# Snap4_audio.net
KiCad netlist of a schematic drawn in Altium Designer
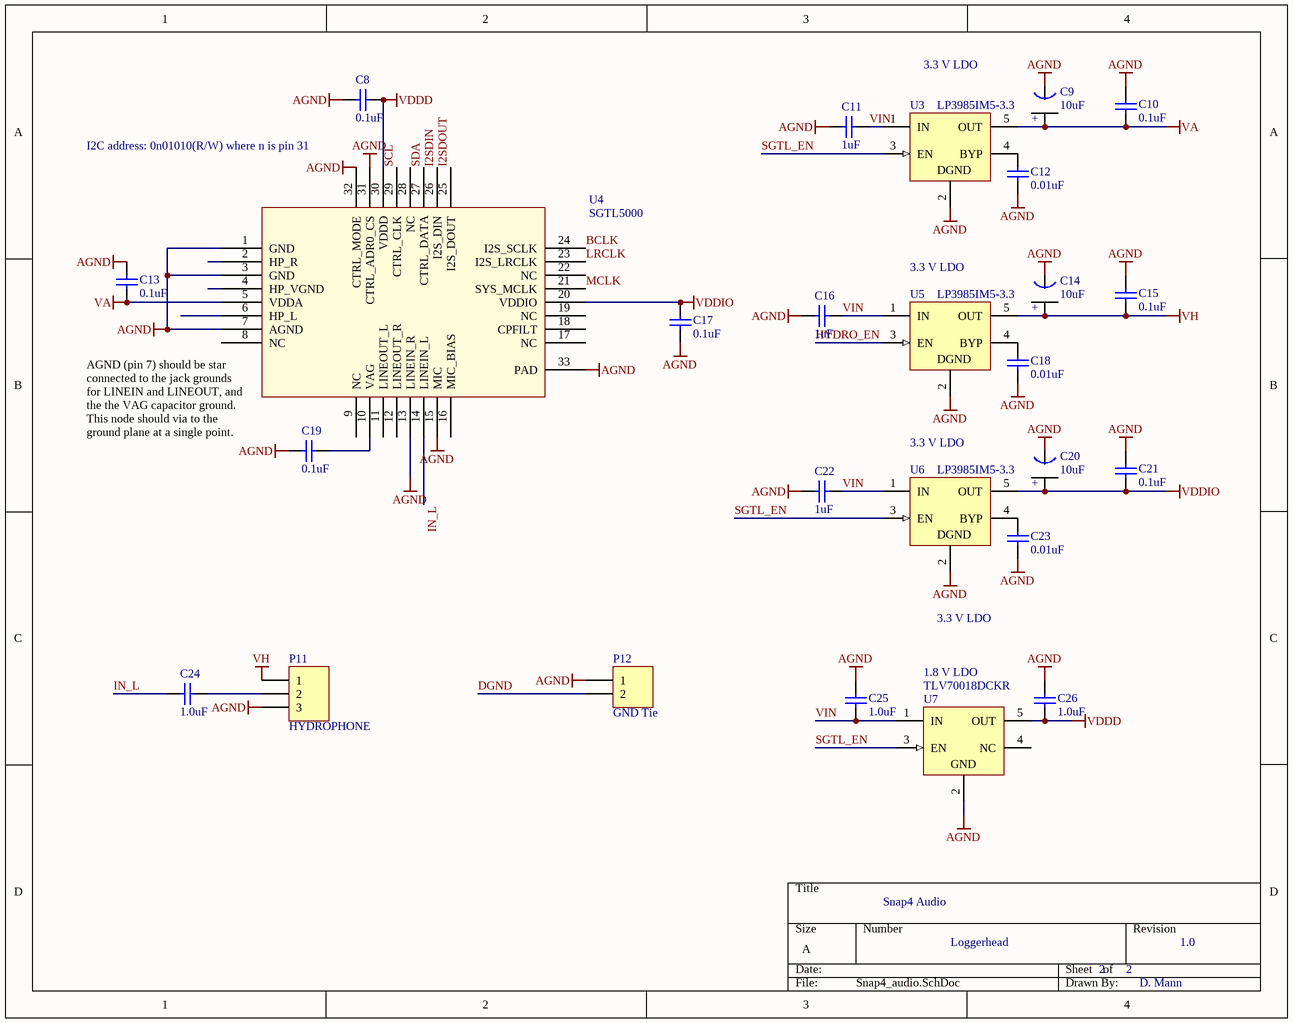
[diagram p0: Snap4_audio.SchDoc]

(export (version "E")
  (design (tool "Eeschema 10.0.6"))
  (components
    (comp (ref "C8")
      (value "0.1uF")
      (footprint "0402")
      (description "Ceramic Chip Capacitor - Standard")
      (fields (field (name "PUBLISHER") "Altium Limited"))
      (libsource (lib "KEMET Chip Capacitor") (part "C0402"))
    )
    (comp (ref "C9") (value "10uF") (footprint "Tant0805") (libsource (lib "Loggerhead") (part "Tant0805")))
    (comp (ref "C10")
      (value "0.1uF")
      (footprint "0402")
      (description "Ceramic Chip Capacitor - Standard")
      (fields (field (name "PUBLISHER") "Altium Limited"))
      (libsource (lib "KEMET Chip Capacitor") (part "C0402"))
    )
    (comp (ref "C11")
      (value "1uF")
      (footprint "0402")
      (description "Ceramic Chip Capacitor - Standard")
      (fields (field (name "PUBLISHER") "Altium Limited"))
      (libsource (lib "KEMET Chip Capacitor") (part "C0402"))
    )
    (comp (ref "C12")
      (value "0.01uF")
      (footprint "0402")
      (description "Ceramic Chip Capacitor - Standard")
      (fields (field (name "PUBLISHER") "Altium Limited"))
      (libsource (lib "KEMET Chip Capacitor") (part "C0402"))
    )
    (comp (ref "C13")
      (value "0.1uF")
      (footprint "0402")
      (description "Ceramic Chip Capacitor - Standard")
      (fields (field (name "PUBLISHER") "Altium Limited"))
      (libsource (lib "KEMET Chip Capacitor") (part "C0402"))
    )
    (comp (ref "C14") (value "10uF") (footprint "Tant0805") (libsource (lib "Loggerhead") (part "Tant0805")))
    (comp (ref "C15")
      (value "0.1uF")
      (footprint "0402")
      (description "Ceramic Chip Capacitor - Standard")
      (fields (field (name "PUBLISHER") "Altium Limited"))
      (libsource (lib "KEMET Chip Capacitor") (part "C0402"))
    )
    (comp (ref "C16")
      (value "1uF")
      (footprint "0402")
      (description "Ceramic Chip Capacitor - Standard")
      (fields (field (name "PUBLISHER") "Altium Limited"))
      (libsource (lib "KEMET Chip Capacitor") (part "C0402"))
    )
    (comp (ref "C17")
      (value "0.1uF")
      (footprint "0402")
      (description "Ceramic Chip Capacitor - Standard")
      (fields (field (name "PUBLISHER") "Altium Limited"))
      (libsource (lib "KEMET Chip Capacitor") (part "C0402"))
    )
    (comp (ref "C18")
      (value "0.01uF")
      (footprint "0402")
      (description "Ceramic Chip Capacitor - Standard")
      (fields (field (name "PUBLISHER") "Altium Limited"))
      (libsource (lib "KEMET Chip Capacitor") (part "C0402"))
    )
    (comp (ref "C19")
      (value "0.1uF")
      (footprint "0402")
      (description "Ceramic Chip Capacitor - Standard")
      (fields (field (name "PUBLISHER") "Altium Limited"))
      (libsource (lib "KEMET Chip Capacitor") (part "C0402"))
    )
    (comp (ref "C20") (value "10uF") (footprint "Tant0805") (libsource (lib "Loggerhead") (part "Tant0805")))
    (comp (ref "C21")
      (value "0.1uF")
      (footprint "0402")
      (description "Ceramic Chip Capacitor - Standard")
      (fields (field (name "PUBLISHER") "Altium Limited"))
      (libsource (lib "KEMET Chip Capacitor") (part "C0402"))
    )
    (comp (ref "C22")
      (value "1uF")
      (footprint "0402")
      (description "Ceramic Chip Capacitor - Standard")
      (fields (field (name "PUBLISHER") "Altium Limited"))
      (libsource (lib "KEMET Chip Capacitor") (part "C0402"))
    )
    (comp (ref "C23")
      (value "0.01uF")
      (footprint "0402")
      (description "Ceramic Chip Capacitor - Standard")
      (fields (field (name "PUBLISHER") "Altium Limited"))
      (libsource (lib "KEMET Chip Capacitor") (part "C0402"))
    )
    (comp (ref "C24")
      (value "1.0uF")
      (footprint "0402")
      (description "Ceramic Chip Capacitor - Standard")
      (fields (field (name "PUBLISHER") "Altium Limited"))
      (libsource (lib "KEMET Chip Capacitor") (part "C0402"))
    )
    (comp (ref "C25")
      (value "1.0uF")
      (footprint "0402")
      (description "Ceramic Chip Capacitor - Standard")
      (fields (field (name "PUBLISHER") "Altium Limited"))
      (libsource (lib "KEMET Chip Capacitor") (part "C0402"))
    )
    (comp (ref "C26")
      (value "1.0uF")
      (footprint "0402")
      (description "Ceramic Chip Capacitor - Standard")
      (fields (field (name "PUBLISHER") "Altium Limited"))
      (libsource (lib "KEMET Chip Capacitor") (part "C0402"))
    )
    (comp (ref "P11")
      (value "HYDROPHONE")
      (footprint "HDR1X3")
      (description "Header, 3-Pin")
      (fields (field (name "PUBLISHER") "Altium Limited"))
      (libsource (lib "Miscellaneous Connectors") (part "Header 3"))
    )
    (comp (ref "P12")
      (value "GND Tie")
      (footprint "HDR1X2")
      (description "Header, 2-Pin")
      (fields (field (name "PUBLISHER") "Altium Limited"))
      (libsource (lib "Miscellaneous Connectors") (part "Header 2"))
    )
    (comp (ref "U3")
      (value "LP3985IM5-3.3")
      (footprint "MF05A_N")
      (description "Micropower, 150mA Low-Noise Ultra Low-Dropout CMOS Voltage Regulator")
      (fields
        (field (name "MANUFACTURER") "National Semiconductor")
        (field (name "DIGIKEYPARTNUMBER") "LP3985IM5-3.3CT-ND")
        (field (name "PUBLISHER") "Altium Limited")
      )
      (libsource (lib "NSC LDO") (part "LP3985IM5-3.3"))
    )
    (comp (ref "U4") (value "SGTL5000") (footprint "QFN32") (libsource (lib "Loggerhead") (part "SGTL5000")))
    (comp (ref "U5")
      (value "LP3985IM5-3.3")
      (footprint "MF05A_N")
      (description "Micropower, 150mA Low-Noise Ultra Low-Dropout CMOS Voltage Regulator")
      (fields
        (field (name "MANUFACTURER") "National Semiconductor")
        (field (name "DIGIKEYPARTNUMBER") "LP3985IM5-3.3CT-ND")
        (field (name "PUBLISHER") "Altium Limited")
      )
      (libsource (lib "NSC LDO") (part "LP3985IM5-3.3"))
    )
    (comp (ref "U6")
      (value "LP3985IM5-3.3")
      (footprint "MF05A_N")
      (description "Micropower, 150mA Low-Noise Ultra Low-Dropout CMOS Voltage Regulator")
      (fields
        (field (name "MANUFACTURER") "National Semiconductor")
        (field (name "DIGIKEYPARTNUMBER") "LP3985IM5-3.3CT-ND")
        (field (name "PUBLISHER") "Altium Limited")
      )
      (libsource (lib "NSC LDO") (part "LP3985IM5-3.3"))
    )
    (comp (ref "U7")
      (value "TLV70018DCKR")
      (footprint "TI-DCK5_V")
      (fields (field (name "MANUFACTURER") "Texas Instruments"))
      (libsource (lib "TI Power Management Linear Regulator Single Channel LDO (0-350mA)") (part "TLV70018DCKR"))
    )
  )
  (nets
    (net (code "1") (name "/BCLK") (class "Default")
      (node (ref "U4") (pin "24") (pinfunction "I2S_SCLK_24") (pintype "passive"))
    )
    (net (code "2") (name "/DGND") (class "Default")
      (node (ref "P12") (pin "2") (pinfunction "2_2") (pintype "passive"))
    )
    (net (code "3") (name "/HYDRO_EN") (class "Default")
      (node (ref "U5") (pin "3") (pinfunction "EN_3") (pintype "input"))
    )
    (net (code "4") (name "/I2SDIN") (class "Default")
      (node (ref "U4") (pin "26") (pinfunction "I2S_DIN_26") (pintype "passive"))
    )
    (net (code "5") (name "/I2SDOUT") (class "Default")
      (node (ref "U4") (pin "25") (pinfunction "I2S_DOUT_25") (pintype "passive"))
    )
    (net (code "6") (name "/IN_L") (class "Default")
      (node (ref "C24") (pin "2") (pinfunction "2_2") (pintype "passive"))
      (node (ref "U4") (pin "14") (pinfunction "LINEIN_L_14") (pintype "passive"))
    )
    (net (code "7") (name "/LRCLK") (class "Default")
      (node (ref "U4") (pin "23") (pinfunction "I2S_LRCLK_23") (pintype "passive"))
    )
    (net (code "8") (name "/MCLK") (class "Default")
      (node (ref "U4") (pin "21") (pinfunction "SYS_MCLK_21") (pintype "passive"))
    )
    (net (code "9") (name "/SCL") (class "Default")
      (node (ref "U4") (pin "29") (pinfunction "CTRL_CLK_29") (pintype "passive"))
    )
    (net (code "10") (name "/SDA") (class "Default")
      (node (ref "U4") (pin "27") (pinfunction "CTRL_DATA_27") (pintype "passive"))
    )
    (net (code "11") (name "/SGTL_EN") (class "Default")
      (node (ref "U3") (pin "3") (pinfunction "EN_3") (pintype "input"))
      (node (ref "U6") (pin "3") (pinfunction "EN_3") (pintype "input"))
      (node (ref "U7") (pin "3") (pinfunction "EN_3") (pintype "input"))
    )
    (net (code "12") (name "/VIN") (class "Default")
      (node (ref "C11") (pin "1") (pinfunction "1_1") (pintype "passive"))
      (node (ref "C16") (pin "1") (pinfunction "1_1") (pintype "passive"))
      (node (ref "C22") (pin "1") (pinfunction "1_1") (pintype "passive"))
      (node (ref "C25") (pin "1") (pinfunction "1_1") (pintype "passive"))
      (node (ref "U3") (pin "1") (pinfunction "IN_1") (pintype "power_in"))
      (node (ref "U5") (pin "1") (pinfunction "IN_1") (pintype "power_in"))
      (node (ref "U6") (pin "1") (pinfunction "IN_1") (pintype "power_in"))
      (node (ref "U7") (pin "1") (pinfunction "IN_1") (pintype "power_in"))
    )
    (net (code "13") (name "AGND") (class "Default")
      (node (ref "C10") (pin "2") (pinfunction "2_2") (pintype "passive"))
      (node (ref "C11") (pin "2") (pinfunction "2_2") (pintype "passive"))
      (node (ref "C12") (pin "2") (pinfunction "2_2") (pintype "passive"))
      (node (ref "C13") (pin "2") (pinfunction "2_2") (pintype "passive"))
      (node (ref "C14") (pin "1") (pinfunction "GND_1") (pintype "passive"))
      (node (ref "C15") (pin "2") (pinfunction "2_2") (pintype "passive"))
      (node (ref "C16") (pin "2") (pinfunction "2_2") (pintype "passive"))
      (node (ref "C17") (pin "2") (pinfunction "2_2") (pintype "passive"))
      (node (ref "C18") (pin "2") (pinfunction "2_2") (pintype "passive"))
      (node (ref "C19") (pin "2") (pinfunction "2_2") (pintype "passive"))
      (node (ref "C20") (pin "1") (pinfunction "GND_1") (pintype "passive"))
      (node (ref "C21") (pin "2") (pinfunction "2_2") (pintype "passive"))
      (node (ref "C22") (pin "2") (pinfunction "2_2") (pintype "passive"))
      (node (ref "C23") (pin "2") (pinfunction "2_2") (pintype "passive"))
      (node (ref "C25") (pin "2") (pinfunction "2_2") (pintype "passive"))
      (node (ref "C26") (pin "2") (pinfunction "2_2") (pintype "passive"))
      (node (ref "C8") (pin "2") (pinfunction "2_2") (pintype "passive"))
      (node (ref "C9") (pin "1") (pinfunction "GND_1") (pintype "passive"))
      (node (ref "P11") (pin "3") (pinfunction "3_3") (pintype "passive"))
      (node (ref "P12") (pin "1") (pinfunction "1_1") (pintype "passive"))
      (node (ref "U3") (pin "2") (pinfunction "GND_2") (pintype "power_in"))
      (node (ref "U4") (pin "1") (pinfunction "GND_1") (pintype "passive"))
      (node (ref "U4") (pin "13") (pinfunction "LINEIN_R_13") (pintype "passive"))
      (node (ref "U4") (pin "15") (pinfunction "MIC_15") (pintype "passive"))
      (node (ref "U4") (pin "3") (pinfunction "GND_3") (pintype "passive"))
      (node (ref "U4") (pin "31") (pinfunction "CTRL_ADR0_CS_31") (pintype "passive"))
      (node (ref "U4") (pin "32") (pinfunction "CTRL_MODE_32") (pintype "passive"))
      (node (ref "U4") (pin "33") (pinfunction "PAD_33") (pintype "passive"))
      (node (ref "U4") (pin "7") (pinfunction "AGND_7") (pintype "passive"))
      (node (ref "U5") (pin "2") (pinfunction "GND_2") (pintype "power_in"))
      (node (ref "U6") (pin "2") (pinfunction "GND_2") (pintype "power_in"))
      (node (ref "U7") (pin "2") (pinfunction "GND_2") (pintype "power_in"))
    )
    (net (code "14") (name "Net-(C24-Pad1)") (class "Default")
      (node (ref "C24") (pin "1") (pinfunction "1_1") (pintype "passive"))
      (node (ref "P11") (pin "2") (pinfunction "2_2") (pintype "passive"))
    )
    (net (code "15") (name "Net-(U3-BYP)") (class "Default")
      (node (ref "C12") (pin "1") (pinfunction "1_1") (pintype "passive"))
      (node (ref "U3") (pin "4") (pinfunction "BYP_4") (pintype "passive"))
    )
    (net (code "16") (name "Net-(U4-VAG)") (class "Default")
      (node (ref "C19") (pin "1") (pinfunction "1_1") (pintype "passive"))
      (node (ref "U4") (pin "10") (pinfunction "VAG_10") (pintype "passive"))
    )
    (net (code "17") (name "Net-(U5-BYP)") (class "Default")
      (node (ref "C18") (pin "1") (pinfunction "1_1") (pintype "passive"))
      (node (ref "U5") (pin "4") (pinfunction "BYP_4") (pintype "passive"))
    )
    (net (code "18") (name "Net-(U6-BYP)") (class "Default")
      (node (ref "C23") (pin "1") (pinfunction "1_1") (pintype "passive"))
      (node (ref "U6") (pin "4") (pinfunction "BYP_4") (pintype "passive"))
    )
    (net (code "19") (name "VA") (class "Default")
      (node (ref "C10") (pin "1") (pinfunction "1_1") (pintype "passive"))
      (node (ref "C13") (pin "1") (pinfunction "1_1") (pintype "passive"))
      (node (ref "C9") (pin "2") (pinfunction "+_2") (pintype "passive"))
      (node (ref "U3") (pin "5") (pinfunction "OUT_5") (pintype "power_in"))
      (node (ref "U4") (pin "5") (pinfunction "VDDA_5") (pintype "passive"))
    )
    (net (code "20") (name "VDDD") (class "Default")
      (node (ref "C26") (pin "1") (pinfunction "1_1") (pintype "passive"))
      (node (ref "C8") (pin "1") (pinfunction "1_1") (pintype "passive"))
      (node (ref "U4") (pin "30") (pinfunction "VDDD_30") (pintype "passive"))
      (node (ref "U7") (pin "5") (pinfunction "OUT_5") (pintype "power_in"))
    )
    (net (code "21") (name "VDDIO") (class "Default")
      (node (ref "C17") (pin "1") (pinfunction "1_1") (pintype "passive"))
      (node (ref "C20") (pin "2") (pinfunction "+_2") (pintype "passive"))
      (node (ref "C21") (pin "1") (pinfunction "1_1") (pintype "passive"))
      (node (ref "U4") (pin "20") (pinfunction "VDDIO_20") (pintype "passive"))
      (node (ref "U6") (pin "5") (pinfunction "OUT_5") (pintype "power_in"))
    )
    (net (code "22") (name "VH") (class "Default")
      (node (ref "C14") (pin "2") (pinfunction "+_2") (pintype "passive"))
      (node (ref "C15") (pin "1") (pinfunction "1_1") (pintype "passive"))
      (node (ref "P11") (pin "1") (pinfunction "1_1") (pintype "passive"))
      (node (ref "U5") (pin "5") (pinfunction "OUT_5") (pintype "power_in"))
    )
    (net (code "23") (name "unconnected-(U4-CPFILT-Pad18)") (class "Default")
      (node (ref "U4") (pin "18") (pinfunction "CPFILT_18") (pintype "passive"))
    )
    (net (code "24") (name "unconnected-(U4-HP_L-Pad6)") (class "Default")
      (node (ref "U4") (pin "6") (pinfunction "HP_L_6") (pintype "passive"))
    )
    (net (code "25") (name "unconnected-(U4-HP_R-Pad2)") (class "Default")
      (node (ref "U4") (pin "2") (pinfunction "HP_R_2") (pintype "passive"))
    )
    (net (code "26") (name "unconnected-(U4-HP_VGND-Pad4)") (class "Default")
      (node (ref "U4") (pin "4") (pinfunction "HP_VGND_4") (pintype "passive"))
    )
    (net (code "27") (name "unconnected-(U4-LINEOUT_L-Pad11)") (class "Default")
      (node (ref "U4") (pin "11") (pinfunction "LINEOUT_L_11") (pintype "passive"))
    )
    (net (code "28") (name "unconnected-(U4-LINEOUT_R-Pad12)") (class "Default")
      (node (ref "U4") (pin "12") (pinfunction "LINEOUT_R_12") (pintype "passive"))
    )
    (net (code "29") (name "unconnected-(U4-MIC_BIAS-Pad16)") (class "Default")
      (node (ref "U4") (pin "16") (pinfunction "MIC_BIAS_16") (pintype "passive"))
    )
    (net (code "30") (name "unconnected-(U4-NC-Pad8)") (class "Default")
      (node (ref "U4") (pin "8") (pinfunction "NC_8") (pintype "passive"))
    )
    (net (code "31") (name "unconnected-(U4-NC-Pad9)") (class "Default")
      (node (ref "U4") (pin "9") (pinfunction "NC_9") (pintype "passive"))
    )
    (net (code "32") (name "unconnected-(U4-NC-Pad17)") (class "Default")
      (node (ref "U4") (pin "17") (pinfunction "NC_17") (pintype "passive"))
    )
    (net (code "33") (name "unconnected-(U4-NC-Pad19)") (class "Default")
      (node (ref "U4") (pin "19") (pinfunction "NC_19") (pintype "passive"))
    )
    (net (code "34") (name "unconnected-(U4-NC-Pad22)") (class "Default")
      (node (ref "U4") (pin "22") (pinfunction "NC_22") (pintype "passive"))
    )
    (net (code "35") (name "unconnected-(U4-NC-Pad28)") (class "Default")
      (node (ref "U4") (pin "28") (pinfunction "NC_28") (pintype "passive"))
    )
    (net (code "36") (name "unconnected-(U7-NC-Pad4)") (class "Default")
      (node (ref "U7") (pin "4") (pinfunction "NC_4") (pintype "passive"))
    )
  )
)
